# Hall_Effect_Surface_Mount_no_AH9251.net
KiCad netlist of a schematic drawn in EAGLE
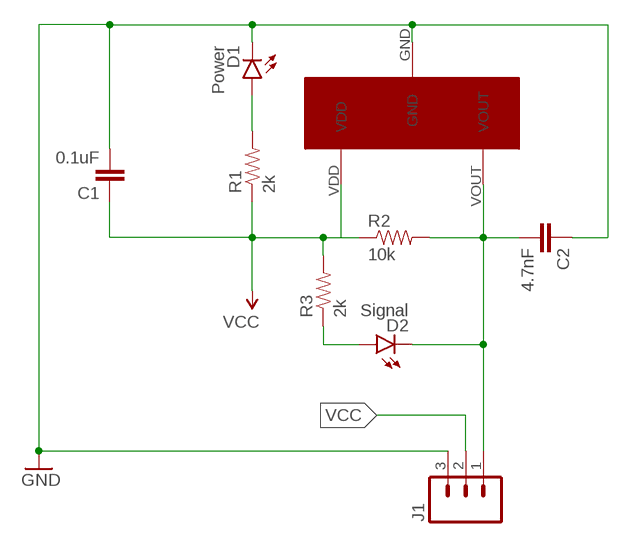
[diagram p0: schematic, sheet 1]

(export (version "E")
  (design (tool "Eeschema 10.0.6"))
  (components
    (comp (ref "C1")
      (value "0.1uF")
      (footprint "eagle-import:0603-CAP")
      (libsource (lib "eagle-import") (part "CAP0603-CAP"))
    )
    (comp (ref "C2")
      (value "4.7nF")
      (footprint "eagle-import:0603-CAP")
      (libsource (lib "eagle-import") (part "CAP0603-CAP"))
    )
    (comp (ref "D1")
      (value "Power")
      (footprint "eagle-import:LED-0603")
      (libsource (lib "eagle-import") (part "LED0603"))
    )
    (comp (ref "D2")
      (value "Signal")
      (footprint "eagle-import:LED-0603")
      (libsource (lib "eagle-import") (part "LED0603"))
    )
    (comp (ref "J1")
      (value "M03PTH")
      (footprint "eagle-import:1X03")
      (libsource (lib "eagle-import") (part "M03PTH"))
    )
    (comp (ref "R1")
      (value "2k")
      (footprint "eagle-import:0603-RES")
      (libsource (lib "eagle-import") (part "RESISTOR0603-RES"))
    )
    (comp (ref "R2")
      (value "10k")
      (footprint "eagle-import:0603-RES")
      (libsource (lib "eagle-import") (part "RESISTOR0603-RES"))
    )
    (comp (ref "R3")
      (value "2k")
      (footprint "eagle-import:0603-RES")
      (libsource (lib "eagle-import") (part "RESISTOR0603-RES"))
    )
    (comp (ref "U$1")
      (value "US5881-HALL-EFFECT")
      (footprint "eagle-import:US5881-HALL-EFFECT")
      (libsource (lib "eagle-import") (part "US5881-HALL-EFFECT"))
    )
  )
  (nets
    (net (code "1") (name "GND") (class "Default")
      (node (ref "C1") (pin "2") (pinfunction "2_2") (pintype "passive"))
      (node (ref "C2") (pin "1") (pinfunction "1_1") (pintype "passive"))
      (node (ref "D1") (pin "C") (pinfunction "C_C") (pintype "passive"))
      (node (ref "J1") (pin "3") (pinfunction "3_3") (pintype "passive"))
      (node (ref "U$1") (pin "GND") (pinfunction "GND_GND") (pintype "bidirectional"))
    )
    (net (code "2") (name "Net-(C2-Pad2)") (class "Default")
      (node (ref "C2") (pin "2") (pinfunction "2_2") (pintype "passive"))
      (node (ref "D2") (pin "C") (pinfunction "C_C") (pintype "passive"))
      (node (ref "J1") (pin "1") (pinfunction "1_1") (pintype "passive"))
      (node (ref "R2") (pin "2") (pinfunction "2_2") (pintype "passive"))
      (node (ref "U$1") (pin "VOUT") (pinfunction "VOUT_VOUT") (pintype "bidirectional"))
    )
    (net (code "3") (name "Net-(D1-PadA)") (class "Default")
      (node (ref "D1") (pin "A") (pinfunction "A_A") (pintype "passive"))
      (node (ref "R1") (pin "2") (pinfunction "2_2") (pintype "passive"))
    )
    (net (code "4") (name "Net-(D2-PadA)") (class "Default")
      (node (ref "D2") (pin "A") (pinfunction "A_A") (pintype "passive"))
      (node (ref "R3") (pin "1") (pinfunction "1_1") (pintype "passive"))
    )
    (net (code "5") (name "VCC") (class "Default")
      (node (ref "C1") (pin "1") (pinfunction "1_1") (pintype "passive"))
      (node (ref "J1") (pin "2") (pinfunction "2_2") (pintype "passive"))
      (node (ref "R1") (pin "1") (pinfunction "1_1") (pintype "passive"))
      (node (ref "R2") (pin "1") (pinfunction "1_1") (pintype "passive"))
      (node (ref "R3") (pin "2") (pinfunction "2_2") (pintype "passive"))
      (node (ref "U$1") (pin "VDD") (pinfunction "VDD_VDD") (pintype "bidirectional"))
    )
  )
)
